# duck.net
KiCad netlist of a schematic drawn in EAGLE
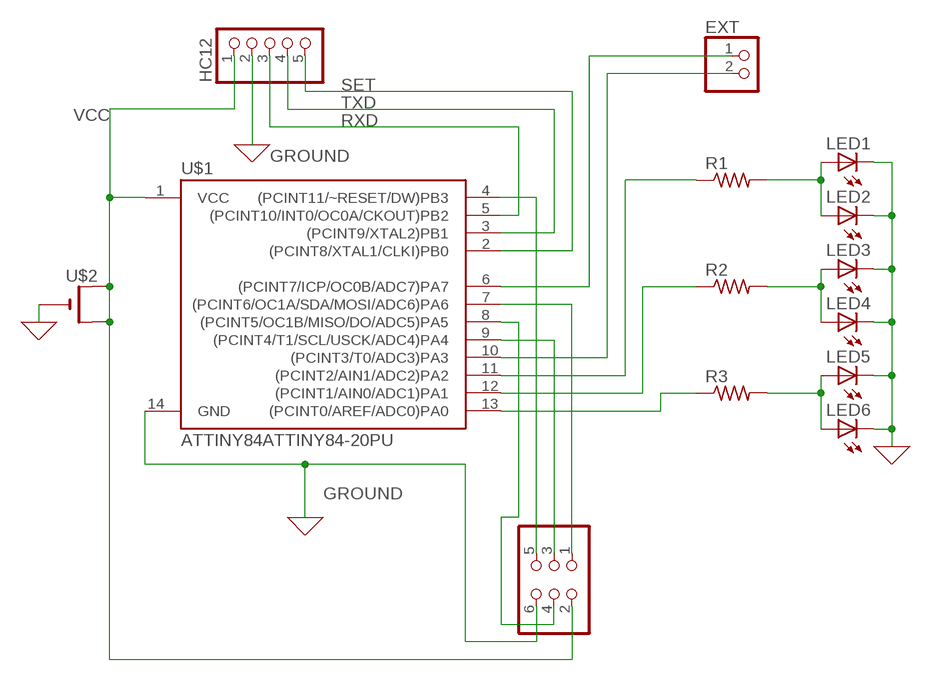
[diagram p0: schematic, sheet 1]

(export (version "E")
  (design (tool "Eeschema 10.0.6"))
  (components
    (comp (ref "DEV")
      (value "PINHD-2X3")
      (footprint "eagle-import:2X03")
      (libsource (lib "eagle-import") (part "PINHD-2X3"))
    )
    (comp (ref "EXT")
      (value "PINHD-1X2")
      (footprint "eagle-import:1X02")
      (libsource (lib "eagle-import") (part "PINHD-1X2"))
    )
    (comp (ref "HC12")
      (value "PINHD-1X5")
      (footprint "eagle-import:1X05")
      (libsource (lib "eagle-import") (part "PINHD-1X5"))
    )
    (comp (ref "LED1")
      (value "LED3MM")
      (footprint "eagle-import:LED3MM")
      (libsource (lib "eagle-import") (part "LED3MM"))
    )
    (comp (ref "LED2")
      (value "LED3MM")
      (footprint "eagle-import:LED3MM")
      (libsource (lib "eagle-import") (part "LED3MM"))
    )
    (comp (ref "LED3")
      (value "LED3MM")
      (footprint "eagle-import:LED3MM")
      (libsource (lib "eagle-import") (part "LED3MM"))
    )
    (comp (ref "LED4")
      (value "LED3MM")
      (footprint "eagle-import:LED3MM")
      (libsource (lib "eagle-import") (part "LED3MM"))
    )
    (comp (ref "LED5")
      (value "LED3MM")
      (footprint "eagle-import:LED3MM")
      (libsource (lib "eagle-import") (part "LED3MM"))
    )
    (comp (ref "LED6")
      (value "LED3MM")
      (footprint "eagle-import:LED3MM")
      (libsource (lib "eagle-import") (part "LED3MM"))
    )
    (comp (ref "R1")
      (value "R-US_0204/7")
      (footprint "eagle-import:0204_7")
      (libsource (lib "eagle-import") (part "R-US_0204/7"))
    )
    (comp (ref "R2")
      (value "R-US_0204/7")
      (footprint "eagle-import:0204_7")
      (libsource (lib "eagle-import") (part "R-US_0204/7"))
    )
    (comp (ref "R3")
      (value "R-US_0204/7")
      (footprint "eagle-import:0204_7")
      (libsource (lib "eagle-import") (part "R-US_0204/7"))
    )
    (comp (ref "U$1")
      (value "ATTINY84ATTINY84-20PU")
      (footprint "eagle-import:DIP14")
      (libsource (lib "eagle-import") (part "ATTINY84ATTINY84-20PU"))
    )
    (comp (ref "U$2")
      (value "CR1220THM")
      (footprint "eagle-import:CR1220-THM")
      (libsource (lib "eagle-import") (part "CR1220THM"))
    )
  )
  (nets
    (net (code "1") (name "/RXD") (class "Default")
      (node (ref "HC12") (pin "3") (pinfunction "3_3") (pintype "passive"))
      (node (ref "U$1") (pin "5") (pinfunction "(PCINT10/INT0/OC0A/CKOUT)PB2_5") (pintype "bidirectional"))
    )
    (net (code "2") (name "/SET") (class "Default")
      (node (ref "HC12") (pin "5") (pinfunction "5_5") (pintype "passive"))
      (node (ref "U$1") (pin "2") (pinfunction "(PCINT8/XTAL1/CLKI)PB0_2") (pintype "bidirectional"))
    )
    (net (code "3") (name "/TXD") (class "Default")
      (node (ref "HC12") (pin "4") (pinfunction "4_4") (pintype "passive"))
      (node (ref "U$1") (pin "3") (pinfunction "(PCINT9/XTAL2)PB1_3") (pintype "bidirectional"))
    )
    (net (code "4") (name "/VCC") (class "Default")
      (node (ref "DEV") (pin "2") (pinfunction "2_2") (pintype "passive"))
      (node (ref "HC12") (pin "1") (pinfunction "1_1") (pintype "passive"))
      (node (ref "U$1") (pin "1") (pinfunction "VCC_1") (pintype "bidirectional"))
      (node (ref "U$2") (pin "+1") (pinfunction "+_+1") (pintype "passive"))
      (node (ref "U$2") (pin "+2") (pinfunction "+1_+2") (pintype "passive"))
    )
    (net (code "5") (name "GND") (class "Default")
      (node (ref "DEV") (pin "6") (pinfunction "6_6") (pintype "passive"))
      (node (ref "HC12") (pin "2") (pinfunction "2_2") (pintype "passive"))
      (node (ref "LED1") (pin "K") (pinfunction "C_K") (pintype "passive"))
      (node (ref "LED2") (pin "K") (pinfunction "C_K") (pintype "passive"))
      (node (ref "LED3") (pin "K") (pinfunction "C_K") (pintype "passive"))
      (node (ref "LED4") (pin "K") (pinfunction "C_K") (pintype "passive"))
      (node (ref "LED5") (pin "K") (pinfunction "C_K") (pintype "passive"))
      (node (ref "LED6") (pin "K") (pinfunction "C_K") (pintype "passive"))
      (node (ref "U$1") (pin "14") (pinfunction "GND_14") (pintype "bidirectional"))
      (node (ref "U$2") (pin "-") (pinfunction "-_-") (pintype "passive"))
    )
    (net (code "6") (name "Net-(LED1-PadA)") (class "Default")
      (node (ref "LED1") (pin "A") (pinfunction "A_A") (pintype "passive"))
      (node (ref "LED2") (pin "A") (pinfunction "A_A") (pintype "passive"))
      (node (ref "R1") (pin "2") (pinfunction "2_2") (pintype "passive"))
    )
    (net (code "7") (name "Net-(LED3-PadA)") (class "Default")
      (node (ref "LED3") (pin "A") (pinfunction "A_A") (pintype "passive"))
      (node (ref "LED4") (pin "A") (pinfunction "A_A") (pintype "passive"))
      (node (ref "R2") (pin "2") (pinfunction "2_2") (pintype "passive"))
    )
    (net (code "8") (name "Net-(LED5-PadA)") (class "Default")
      (node (ref "LED5") (pin "A") (pinfunction "A_A") (pintype "passive"))
      (node (ref "LED6") (pin "A") (pinfunction "A_A") (pintype "passive"))
      (node (ref "R3") (pin "2") (pinfunction "2_2") (pintype "passive"))
    )
    (net (code "9") (name "Net-(U$1-(PCINT0{slash}AREF{slash}ADC0)PA0)") (class "Default")
      (node (ref "R3") (pin "1") (pinfunction "1_1") (pintype "passive"))
      (node (ref "U$1") (pin "13") (pinfunction "(PCINT0/AREF/ADC0)PA0_13") (pintype "bidirectional"))
    )
    (net (code "10") (name "Net-(U$1-(PCINT1{slash}AIN0{slash}ADC1)PA1)") (class "Default")
      (node (ref "R2") (pin "1") (pinfunction "1_1") (pintype "passive"))
      (node (ref "U$1") (pin "12") (pinfunction "(PCINT1/AIN0/ADC1)PA1_12") (pintype "bidirectional"))
    )
    (net (code "11") (name "Net-(U$1-(PCINT2{slash}AIN1{slash}ADC2)PA2)") (class "Default")
      (node (ref "R1") (pin "1") (pinfunction "1_1") (pintype "passive"))
      (node (ref "U$1") (pin "11") (pinfunction "(PCINT2/AIN1/ADC2)PA2_11") (pintype "bidirectional"))
    )
    (net (code "12") (name "Net-(U$1-(PCINT3{slash}T0{slash}ADC3)PA3)") (class "Default")
      (node (ref "EXT") (pin "2") (pinfunction "2_2") (pintype "passive"))
      (node (ref "U$1") (pin "10") (pinfunction "(PCINT3/T0/ADC3)PA3_10") (pintype "bidirectional"))
    )
    (net (code "13") (name "Net-(U$1-(PCINT4{slash}T1{slash}SCL{slash}USCK{slash}ADC4)PA4)") (class "Default")
      (node (ref "DEV") (pin "3") (pinfunction "3_3") (pintype "passive"))
      (node (ref "U$1") (pin "9") (pinfunction "(PCINT4/T1/SCL/USCK/ADC4)PA4_9") (pintype "bidirectional"))
    )
    (net (code "14") (name "Net-(U$1-(PCINT5{slash}OC1B{slash}MISO{slash}DO{slash}ADC5)PA5)") (class "Default")
      (node (ref "DEV") (pin "4") (pinfunction "4_4") (pintype "passive"))
      (node (ref "U$1") (pin "8") (pinfunction "(PCINT5/OC1B/MISO/DO/ADC5)PA5_8") (pintype "bidirectional"))
    )
    (net (code "15") (name "Net-(U$1-(PCINT6{slash}OC1A{slash}SDA{slash}MOSI{slash}ADC6)PA6)") (class "Default")
      (node (ref "DEV") (pin "1") (pinfunction "1_1") (pintype "passive"))
      (node (ref "U$1") (pin "7") (pinfunction "(PCINT6/OC1A/SDA/MOSI/ADC6)PA6_7") (pintype "bidirectional"))
    )
    (net (code "16") (name "Net-(U$1-(PCINT7{slash}ICP{slash}OC0B{slash}ADC7)PA7)") (class "Default")
      (node (ref "EXT") (pin "1") (pinfunction "1_1") (pintype "passive"))
      (node (ref "U$1") (pin "6") (pinfunction "(PCINT7/ICP/OC0B/ADC7)PA7_6") (pintype "bidirectional"))
    )
    (net (code "17") (name "Net-(U$1-(PCINT11{slash}~{RESET{slash}DW})PB3)") (class "Default")
      (node (ref "DEV") (pin "5") (pinfunction "5_5") (pintype "passive"))
      (node (ref "U$1") (pin "4") (pinfunction "(PCINT11/~{RESET/DW})PB3_4") (pintype "bidirectional"))
    )
  )
)
